# Controller_-_ESP32_Wroom_-_Rev_A.net
KiCad netlist of a schematic drawn in EAGLE
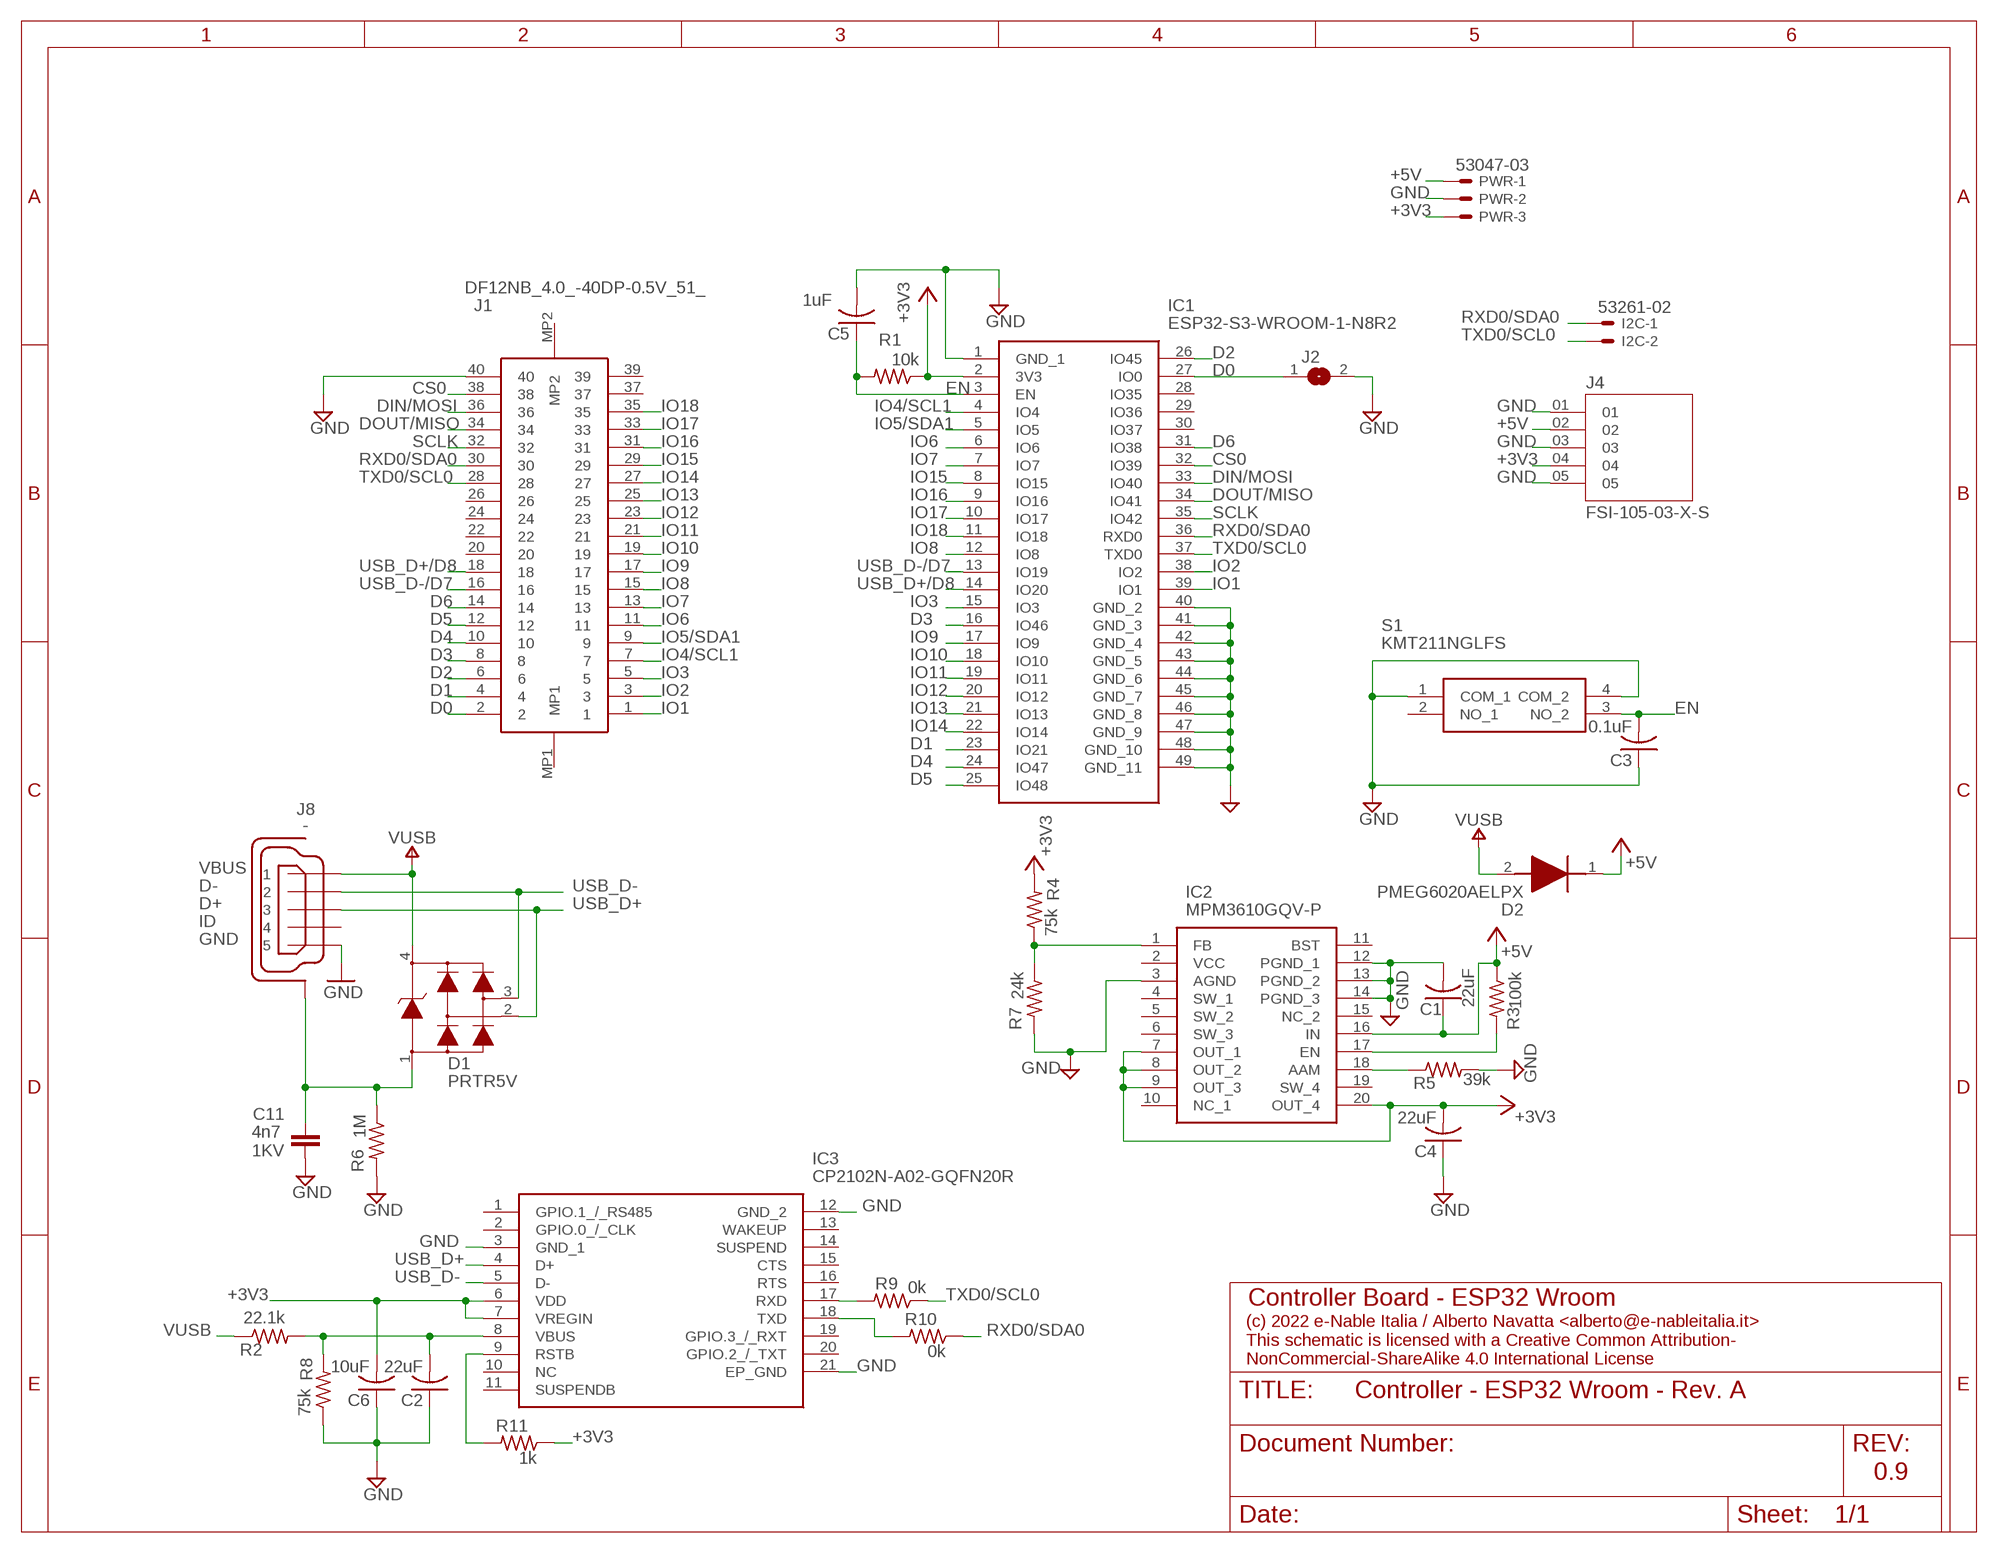
[diagram p0: schematic, sheet 1]

(export (version "E")
  (design (tool "Eeschema 10.0.6"))
  (components
    (comp (ref "C1")
      (value "22uF")
      (footprint "eagle-import:C0603")
      (libsource (lib "eagle-import") (part "C-USC0603"))
    )
    (comp (ref "C2")
      (value "22uF")
      (footprint "eagle-import:C0402")
      (libsource (lib "eagle-import") (part "C-USC0402"))
    )
    (comp (ref "C3")
      (value "0.1uF")
      (footprint "eagle-import:C0402")
      (libsource (lib "eagle-import") (part "C-USC0402"))
    )
    (comp (ref "C4")
      (value "22uF")
      (footprint "eagle-import:C0603")
      (libsource (lib "eagle-import") (part "C-USC0603"))
    )
    (comp (ref "C5")
      (value "1uF")
      (footprint "eagle-import:C0402")
      (libsource (lib "eagle-import") (part "C-USC0402"))
    )
    (comp (ref "C6")
      (value "10uF")
      (footprint "eagle-import:C0402")
      (libsource (lib "eagle-import") (part "C-USC0402"))
    )
    (comp (ref "C11")
      (value "4n7")
      (footprint "eagle-import:0805-R2013X50N")
      (fields (field (name "MANUFACTURER") "Kemet") (field (name "VOLTAGE") "1KV"))
      (libsource (lib "eagle-import") (part "C-08054.7NF"))
    )
    (comp (ref "D1")
      (value "PRTR5V")
      (footprint "eagle-import:SOT190P230X110-4N")
      (fields (field (name "MANUFACTURER") "NXP"))
      (libsource (lib "eagle-import") (part "PRTR5V0U2X,215"))
    )
    (comp (ref "D2")
      (value "PMEG6020AELPX")
      (footprint "eagle-import:SODFL4725X110N")
      (fields (field (name "MOUSER_PART_NUMBER") "771-PMEG6020AELPX"))
      (libsource (lib "eagle-import") (part "PMEG6020AELPX"))
    )
    (comp (ref "I2C")
      (value "53261-02")
      (footprint "eagle-import:53261-02")
      (fields (field (name "MF") "MOLEX"))
      (libsource (lib "eagle-import") (part "53?-02261"))
    )
    (comp (ref "IC1")
      (value "ESP32-S3-WROOM-1-N8R2")
      (footprint "eagle-import:ESP32S3WROOM1N8R2")
      (fields (field (name "MOUSER_PART_NUMBER") "356-ESP32-S3WRM1N8R2"))
      (libsource (lib "eagle-import") (part "ESP32-S3-WROOM-1-N8R2"))
    )
    (comp (ref "IC2")
      (value "MPM3610GQV-P")
      (footprint "eagle-import:MPM3610GQVP")
      (fields (field (name "MOUSER_PART_NUMBER") "946-MPM3610GQV-P"))
      (libsource (lib "eagle-import") (part "MPM3610GQV-P"))
    )
    (comp (ref "IC3")
      (value "CP2102N-A02-GQFN20R")
      (footprint "eagle-import:CP2102NA02GQFN20")
      (fields (field (name "MOUSER_PART_NUMBER") "634-CP2102NA02QFN20R"))
      (libsource (lib "eagle-import") (part "CP2102N-A02-GQFN20R"))
    )
    (comp (ref "J1")
      (value "DF12NB_4.0_-40DP-0.5V_51_")
      (footprint "eagle-import:DF12NB4040DP05V51")
      (fields
        (field (name "MANUFACTURER_PART_NUMBER") "DF12NB(4.0)-40DP-0.5V(51)")
        (field (name "MOUSER_PART_NUMBER") "798-DF12NB4040DP0551")
      )
      (libsource (lib "eagle-import") (part "DF12NB_4.0_-40DP-0.5V_51_"))
    )
    (comp (ref "J2") (value "SJ") (footprint "eagle-import:SJ") (libsource (lib "eagle-import") (part "SJ")))
    (comp (ref "J4")
      (value "FSI-105-03-X-S")
      (footprint "eagle-import:SAMTEC_FSI-105-03-X-S")
      (fields (field (name "MF") "Samtec") (field (name "MP") "FSI-105-03-G-S"))
      (libsource (lib "eagle-import") (part "FSI-105-03-X-S"))
    )
    (comp (ref "J8")
      (value "-")
      (footprint "eagle-import:ZX62-AB-5PA")
      (fields (field (name "MANUFACTURER") "Hirose"))
      (libsource (lib "eagle-import") (part "USB-MICRO"))
    )
    (comp (ref "PWR")
      (value "53047-03")
      (footprint "eagle-import:53047-03")
      (fields (field (name "MF") "MOLEX") (field (name "MPN") "530470310"))
      (libsource (lib "eagle-import") (part "53?-03047"))
    )
    (comp (ref "R1")
      (value "10k")
      (footprint "eagle-import:R0402")
      (libsource (lib "eagle-import") (part "R-US_R0402"))
    )
    (comp (ref "R2")
      (value "22.1k")
      (footprint "eagle-import:R0402")
      (libsource (lib "eagle-import") (part "R-US_R0402"))
    )
    (comp (ref "R3")
      (value "100k")
      (footprint "eagle-import:R0402")
      (libsource (lib "eagle-import") (part "R-US_R0402"))
    )
    (comp (ref "R4")
      (value "75k")
      (footprint "eagle-import:R0402")
      (libsource (lib "eagle-import") (part "R-US_R0402"))
    )
    (comp (ref "R5")
      (value "39k")
      (footprint "eagle-import:R0402")
      (libsource (lib "eagle-import") (part "R-US_R0402"))
    )
    (comp (ref "R6")
      (value "1M")
      (footprint "eagle-import:R0402")
      (libsource (lib "eagle-import") (part "R-US_R0402"))
    )
    (comp (ref "R7")
      (value "24k")
      (footprint "eagle-import:R0402")
      (libsource (lib "eagle-import") (part "R-US_R0402"))
    )
    (comp (ref "R8")
      (value "75k")
      (footprint "eagle-import:R0402")
      (libsource (lib "eagle-import") (part "R-US_R0402"))
    )
    (comp (ref "R9")
      (value "0k")
      (footprint "eagle-import:R0402")
      (libsource (lib "eagle-import") (part "R-US_R0402"))
    )
    (comp (ref "R10")
      (value "0k")
      (footprint "eagle-import:R0402")
      (libsource (lib "eagle-import") (part "R-US_R0402"))
    )
    (comp (ref "R11")
      (value "1k")
      (footprint "eagle-import:R0402")
      (libsource (lib "eagle-import") (part "R-US_R0402"))
    )
    (comp (ref "S1")
      (value "KMT211NGLFS")
      (footprint "eagle-import:KMT211NGLFS")
      (fields (field (name "MOUSER_PART_NUMBER") "611-KMT211NGLFS"))
      (libsource (lib "eagle-import") (part "KMT211NGLFS"))
    )
  )
  (nets
    (net (code "1") (name "+3V3") (class "Default")
      (node (ref "C4") (pin "2") (pinfunction "2_2") (pintype "passive"))
      (node (ref "C6") (pin "2") (pinfunction "2_2") (pintype "passive"))
      (node (ref "IC1") (pin "2") (pinfunction "3V3_2") (pintype "bidirectional"))
      (node (ref "IC2") (pin "20") (pinfunction "OUT_4_20") (pintype "bidirectional"))
      (node (ref "IC2") (pin "7") (pinfunction "OUT_1_7") (pintype "bidirectional"))
      (node (ref "IC2") (pin "8") (pinfunction "OUT_2_8") (pintype "bidirectional"))
      (node (ref "IC2") (pin "9") (pinfunction "OUT_3_9") (pintype "bidirectional"))
      (node (ref "IC3") (pin "6") (pinfunction "VDD_6") (pintype "bidirectional"))
      (node (ref "IC3") (pin "7") (pinfunction "VREGIN_7") (pintype "bidirectional"))
      (node (ref "J4") (pin "04") (pinfunction "04_04") (pintype "passive"))
      (node (ref "PWR") (pin "3") (pinfunction "S_3") (pintype "passive"))
      (node (ref "R1") (pin "1") (pinfunction "1_1") (pintype "passive"))
      (node (ref "R11") (pin "1") (pinfunction "1_1") (pintype "passive"))
      (node (ref "R4") (pin "2") (pinfunction "2_2") (pintype "passive"))
    )
    (net (code "2") (name "+5V") (class "Default")
      (node (ref "C1") (pin "1") (pinfunction "1_1") (pintype "passive"))
      (node (ref "D2") (pin "1") (pinfunction "K_1") (pintype "bidirectional"))
      (node (ref "IC2") (pin "16") (pinfunction "IN_16") (pintype "bidirectional"))
      (node (ref "J4") (pin "02") (pinfunction "02_02") (pintype "passive"))
      (node (ref "PWR") (pin "1") (pinfunction "S_1") (pintype "passive"))
      (node (ref "R3") (pin "1") (pinfunction "1_1") (pintype "passive"))
    )
    (net (code "3") (name "/CS0") (class "Default")
      (node (ref "IC1") (pin "32") (pinfunction "IO39_32") (pintype "bidirectional"))
      (node (ref "J1") (pin "38") (pinfunction "38_38") (pintype "bidirectional"))
    )
    (net (code "4") (name "/D0") (class "Default")
      (node (ref "IC1") (pin "27") (pinfunction "IO0_27") (pintype "bidirectional"))
      (node (ref "J1") (pin "2") (pinfunction "2_2") (pintype "bidirectional"))
      (node (ref "J2") (pin "1") (pinfunction "1_1") (pintype "passive"))
    )
    (net (code "5") (name "/D1") (class "Default")
      (node (ref "IC1") (pin "23") (pinfunction "IO21_23") (pintype "bidirectional"))
      (node (ref "J1") (pin "4") (pinfunction "4_4") (pintype "bidirectional"))
    )
    (net (code "6") (name "/D2") (class "Default")
      (node (ref "IC1") (pin "26") (pinfunction "IO45_26") (pintype "bidirectional"))
      (node (ref "J1") (pin "6") (pinfunction "6_6") (pintype "bidirectional"))
    )
    (net (code "7") (name "/D3") (class "Default")
      (node (ref "IC1") (pin "16") (pinfunction "IO46_16") (pintype "bidirectional"))
      (node (ref "J1") (pin "8") (pinfunction "8_8") (pintype "bidirectional"))
    )
    (net (code "8") (name "/D4") (class "Default")
      (node (ref "IC1") (pin "24") (pinfunction "IO47_24") (pintype "bidirectional"))
      (node (ref "J1") (pin "10") (pinfunction "10_10") (pintype "bidirectional"))
    )
    (net (code "9") (name "/D5") (class "Default")
      (node (ref "IC1") (pin "25") (pinfunction "IO48_25") (pintype "bidirectional"))
      (node (ref "J1") (pin "12") (pinfunction "12_12") (pintype "bidirectional"))
    )
    (net (code "10") (name "/D6") (class "Default")
      (node (ref "IC1") (pin "31") (pinfunction "IO38_31") (pintype "bidirectional"))
      (node (ref "J1") (pin "14") (pinfunction "14_14") (pintype "bidirectional"))
    )
    (net (code "11") (name "/DIN{slash}MOSI") (class "Default")
      (node (ref "IC1") (pin "33") (pinfunction "IO40_33") (pintype "bidirectional"))
      (node (ref "J1") (pin "36") (pinfunction "36_36") (pintype "bidirectional"))
    )
    (net (code "12") (name "/DOUT{slash}MISO") (class "Default")
      (node (ref "IC1") (pin "34") (pinfunction "IO41_34") (pintype "bidirectional"))
      (node (ref "J1") (pin "34") (pinfunction "34_34") (pintype "bidirectional"))
    )
    (net (code "13") (name "/EN") (class "Default")
      (node (ref "C3") (pin "2") (pinfunction "2_2") (pintype "passive"))
      (node (ref "C5") (pin "1") (pinfunction "1_1") (pintype "passive"))
      (node (ref "IC1") (pin "3") (pinfunction "EN_3") (pintype "bidirectional"))
      (node (ref "R1") (pin "2") (pinfunction "2_2") (pintype "passive"))
      (node (ref "S1") (pin "3") (pinfunction "NO_2_3") (pintype "bidirectional"))
    )
    (net (code "14") (name "/IO1") (class "Default")
      (node (ref "IC1") (pin "39") (pinfunction "IO1_39") (pintype "bidirectional"))
      (node (ref "J1") (pin "1") (pinfunction "1_1") (pintype "bidirectional"))
    )
    (net (code "15") (name "/IO2") (class "Default")
      (node (ref "IC1") (pin "38") (pinfunction "IO2_38") (pintype "bidirectional"))
      (node (ref "J1") (pin "3") (pinfunction "3_3") (pintype "bidirectional"))
    )
    (net (code "16") (name "/IO3") (class "Default")
      (node (ref "IC1") (pin "15") (pinfunction "IO3_15") (pintype "bidirectional"))
      (node (ref "J1") (pin "5") (pinfunction "5_5") (pintype "bidirectional"))
    )
    (net (code "17") (name "/IO4{slash}SCL1") (class "Default")
      (node (ref "IC1") (pin "4") (pinfunction "IO4_4") (pintype "bidirectional"))
      (node (ref "J1") (pin "7") (pinfunction "7_7") (pintype "bidirectional"))
    )
    (net (code "18") (name "/IO5{slash}SDA1") (class "Default")
      (node (ref "IC1") (pin "5") (pinfunction "IO5_5") (pintype "bidirectional"))
      (node (ref "J1") (pin "9") (pinfunction "9_9") (pintype "bidirectional"))
    )
    (net (code "19") (name "/IO6") (class "Default")
      (node (ref "IC1") (pin "6") (pinfunction "IO6_6") (pintype "bidirectional"))
      (node (ref "J1") (pin "11") (pinfunction "11_11") (pintype "bidirectional"))
    )
    (net (code "20") (name "/IO7") (class "Default")
      (node (ref "IC1") (pin "7") (pinfunction "IO7_7") (pintype "bidirectional"))
      (node (ref "J1") (pin "13") (pinfunction "13_13") (pintype "bidirectional"))
    )
    (net (code "21") (name "/IO8") (class "Default")
      (node (ref "IC1") (pin "12") (pinfunction "IO8_12") (pintype "bidirectional"))
      (node (ref "J1") (pin "15") (pinfunction "15_15") (pintype "bidirectional"))
    )
    (net (code "22") (name "/IO9") (class "Default")
      (node (ref "IC1") (pin "17") (pinfunction "IO9_17") (pintype "bidirectional"))
      (node (ref "J1") (pin "17") (pinfunction "17_17") (pintype "bidirectional"))
    )
    (net (code "23") (name "/IO10") (class "Default")
      (node (ref "IC1") (pin "18") (pinfunction "IO10_18") (pintype "bidirectional"))
      (node (ref "J1") (pin "19") (pinfunction "19_19") (pintype "bidirectional"))
    )
    (net (code "24") (name "/IO11") (class "Default")
      (node (ref "IC1") (pin "19") (pinfunction "IO11_19") (pintype "bidirectional"))
      (node (ref "J1") (pin "21") (pinfunction "21_21") (pintype "bidirectional"))
    )
    (net (code "25") (name "/IO12") (class "Default")
      (node (ref "IC1") (pin "20") (pinfunction "IO12_20") (pintype "bidirectional"))
      (node (ref "J1") (pin "23") (pinfunction "23_23") (pintype "bidirectional"))
    )
    (net (code "26") (name "/IO13") (class "Default")
      (node (ref "IC1") (pin "21") (pinfunction "IO13_21") (pintype "bidirectional"))
      (node (ref "J1") (pin "25") (pinfunction "25_25") (pintype "bidirectional"))
    )
    (net (code "27") (name "/IO14") (class "Default")
      (node (ref "IC1") (pin "22") (pinfunction "IO14_22") (pintype "bidirectional"))
      (node (ref "J1") (pin "27") (pinfunction "27_27") (pintype "bidirectional"))
    )
    (net (code "28") (name "/IO15") (class "Default")
      (node (ref "IC1") (pin "8") (pinfunction "IO15_8") (pintype "bidirectional"))
      (node (ref "J1") (pin "29") (pinfunction "29_29") (pintype "bidirectional"))
    )
    (net (code "29") (name "/IO16") (class "Default")
      (node (ref "IC1") (pin "9") (pinfunction "IO16_9") (pintype "bidirectional"))
      (node (ref "J1") (pin "31") (pinfunction "31_31") (pintype "bidirectional"))
    )
    (net (code "30") (name "/IO17") (class "Default")
      (node (ref "IC1") (pin "10") (pinfunction "IO17_10") (pintype "bidirectional"))
      (node (ref "J1") (pin "33") (pinfunction "33_33") (pintype "bidirectional"))
    )
    (net (code "31") (name "/IO18") (class "Default")
      (node (ref "IC1") (pin "11") (pinfunction "IO18_11") (pintype "bidirectional"))
      (node (ref "J1") (pin "35") (pinfunction "35_35") (pintype "bidirectional"))
    )
    (net (code "32") (name "/RXD0{slash}SDA0") (class "Default")
      (node (ref "I2C") (pin "1") (pinfunction "S_1") (pintype "passive"))
      (node (ref "IC1") (pin "36") (pinfunction "RXD0_36") (pintype "bidirectional"))
      (node (ref "J1") (pin "30") (pinfunction "30_30") (pintype "bidirectional"))
      (node (ref "R10") (pin "1") (pinfunction "1_1") (pintype "passive"))
    )
    (net (code "33") (name "/SCLK") (class "Default")
      (node (ref "IC1") (pin "35") (pinfunction "IO42_35") (pintype "bidirectional"))
      (node (ref "J1") (pin "32") (pinfunction "32_32") (pintype "bidirectional"))
    )
    (net (code "34") (name "/TXD0{slash}SCL0") (class "Default")
      (node (ref "I2C") (pin "2") (pinfunction "S_2") (pintype "passive"))
      (node (ref "IC1") (pin "37") (pinfunction "TXD0_37") (pintype "bidirectional"))
      (node (ref "J1") (pin "28") (pinfunction "28_28") (pintype "bidirectional"))
      (node (ref "R9") (pin "1") (pinfunction "1_1") (pintype "passive"))
    )
    (net (code "35") (name "/USB_D+") (class "Default")
      (node (ref "D1") (pin "2") (pinfunction "2_2") (pintype "passive"))
      (node (ref "IC3") (pin "4") (pinfunction "D+_4") (pintype "bidirectional"))
      (node (ref "J8") (pin "3") (pinfunction "3_3") (pintype "passive"))
    )
    (net (code "36") (name "/USB_D+{slash}D8") (class "Default")
      (node (ref "IC1") (pin "14") (pinfunction "IO20_14") (pintype "bidirectional"))
      (node (ref "J1") (pin "18") (pinfunction "18_18") (pintype "bidirectional"))
    )
    (net (code "37") (name "/USB_D-") (class "Default")
      (node (ref "D1") (pin "3") (pinfunction "3_3") (pintype "passive"))
      (node (ref "IC3") (pin "5") (pinfunction "D-_5") (pintype "bidirectional"))
      (node (ref "J8") (pin "2") (pinfunction "2_2") (pintype "passive"))
    )
    (net (code "38") (name "/USB_D-{slash}D7") (class "Default")
      (node (ref "IC1") (pin "13") (pinfunction "IO19_13") (pintype "bidirectional"))
      (node (ref "J1") (pin "16") (pinfunction "16_16") (pintype "bidirectional"))
    )
    (net (code "39") (name "GND") (class "Default")
      (node (ref "C1") (pin "2") (pinfunction "2_2") (pintype "passive"))
      (node (ref "C11") (pin "2") (pinfunction "2_2") (pintype "passive"))
      (node (ref "C2") (pin "1") (pinfunction "1_1") (pintype "passive"))
      (node (ref "C3") (pin "1") (pinfunction "1_1") (pintype "passive"))
      (node (ref "C4") (pin "1") (pinfunction "1_1") (pintype "passive"))
      (node (ref "C5") (pin "2") (pinfunction "2_2") (pintype "passive"))
      (node (ref "C6") (pin "1") (pinfunction "1_1") (pintype "passive"))
      (node (ref "IC1") (pin "1") (pinfunction "GND_1_1") (pintype "bidirectional"))
      (node (ref "IC1") (pin "40") (pinfunction "GND_2_40") (pintype "bidirectional"))
      (node (ref "IC1") (pin "41") (pinfunction "GND_3_41") (pintype "bidirectional"))
      (node (ref "IC1") (pin "42") (pinfunction "GND_4_42") (pintype "bidirectional"))
      (node (ref "IC1") (pin "43") (pinfunction "GND_5_43") (pintype "bidirectional"))
      (node (ref "IC1") (pin "44") (pinfunction "GND_6_44") (pintype "bidirectional"))
      (node (ref "IC1") (pin "45") (pinfunction "GND_7_45") (pintype "bidirectional"))
      (node (ref "IC1") (pin "46") (pinfunction "GND_8_46") (pintype "bidirectional"))
      (node (ref "IC1") (pin "47") (pinfunction "GND_9_47") (pintype "bidirectional"))
      (node (ref "IC1") (pin "48") (pinfunction "GND_10_48") (pintype "bidirectional"))
      (node (ref "IC1") (pin "49") (pinfunction "GND_11_49") (pintype "bidirectional"))
      (node (ref "IC2") (pin "12") (pinfunction "PGND_1_12") (pintype "bidirectional"))
      (node (ref "IC2") (pin "13") (pinfunction "PGND_2_13") (pintype "bidirectional"))
      (node (ref "IC2") (pin "14") (pinfunction "PGND_3_14") (pintype "bidirectional"))
      (node (ref "IC2") (pin "3") (pinfunction "AGND_3") (pintype "bidirectional"))
      (node (ref "IC3") (pin "12") (pinfunction "GND_2_12") (pintype "bidirectional"))
      (node (ref "IC3") (pin "21") (pinfunction "EP_GND_21") (pintype "bidirectional"))
      (node (ref "IC3") (pin "3") (pinfunction "GND_1_3") (pintype "bidirectional"))
      (node (ref "J1") (pin "40") (pinfunction "40_40") (pintype "bidirectional"))
      (node (ref "J2") (pin "2") (pinfunction "2_2") (pintype "passive"))
      (node (ref "J4") (pin "01") (pinfunction "01_01") (pintype "passive"))
      (node (ref "J4") (pin "03") (pinfunction "03_03") (pintype "passive"))
      (node (ref "J4") (pin "05") (pinfunction "05_05") (pintype "passive"))
      (node (ref "J8") (pin "5") (pinfunction "5_5") (pintype "passive"))
      (node (ref "PWR") (pin "2") (pinfunction "S_2") (pintype "passive"))
      (node (ref "R5") (pin "2") (pinfunction "2_2") (pintype "passive"))
      (node (ref "R6") (pin "2") (pinfunction "2_2") (pintype "passive"))
      (node (ref "R7") (pin "2") (pinfunction "2_2") (pintype "passive"))
      (node (ref "R8") (pin "1") (pinfunction "1_1") (pintype "passive"))
      (node (ref "S1") (pin "1") (pinfunction "COM_1_1") (pintype "bidirectional"))
      (node (ref "S1") (pin "4") (pinfunction "COM_2_4") (pintype "bidirectional"))
    )
    (net (code "40") (name "Net-(C11-Pad1)") (class "Default")
      (node (ref "C11") (pin "1") (pinfunction "1_1") (pintype "passive"))
      (node (ref "D1") (pin "1") (pinfunction "1_1") (pintype "passive"))
      (node (ref "J8") (pin "10") (pinfunction "SH_10") (pintype "passive"))
      (node (ref "J8") (pin "11") (pinfunction "SH_11") (pintype "passive"))
      (node (ref "J8") (pin "6") (pinfunction "SH_6") (pintype "passive"))
      (node (ref "J8") (pin "7") (pinfunction "SH_7") (pintype "passive"))
      (node (ref "J8") (pin "8") (pinfunction "SH_8") (pintype "passive"))
      (node (ref "J8") (pin "9") (pinfunction "SH_9") (pintype "passive"))
      (node (ref "R6") (pin "1") (pinfunction "1_1") (pintype "passive"))
    )
    (net (code "41") (name "Net-(IC2-AAM)") (class "Default")
      (node (ref "IC2") (pin "18") (pinfunction "AAM_18") (pintype "bidirectional"))
      (node (ref "R5") (pin "1") (pinfunction "1_1") (pintype "passive"))
    )
    (net (code "42") (name "Net-(IC2-EN)") (class "Default")
      (node (ref "IC2") (pin "17") (pinfunction "EN_17") (pintype "bidirectional"))
      (node (ref "R3") (pin "2") (pinfunction "2_2") (pintype "passive"))
    )
    (net (code "43") (name "Net-(IC2-FB)") (class "Default")
      (node (ref "IC2") (pin "1") (pinfunction "FB_1") (pintype "bidirectional"))
      (node (ref "R4") (pin "1") (pinfunction "1_1") (pintype "passive"))
      (node (ref "R7") (pin "1") (pinfunction "1_1") (pintype "passive"))
    )
    (net (code "44") (name "Net-(IC3-RSTB)") (class "Default")
      (node (ref "IC3") (pin "9") (pinfunction "RSTB_9") (pintype "bidirectional"))
      (node (ref "R11") (pin "2") (pinfunction "2_2") (pintype "passive"))
    )
    (net (code "45") (name "Net-(IC3-RXD)") (class "Default")
      (node (ref "IC3") (pin "17") (pinfunction "RXD_17") (pintype "bidirectional"))
      (node (ref "R9") (pin "2") (pinfunction "2_2") (pintype "passive"))
    )
    (net (code "46") (name "Net-(IC3-TXD)") (class "Default")
      (node (ref "IC3") (pin "18") (pinfunction "TXD_18") (pintype "bidirectional"))
      (node (ref "R10") (pin "2") (pinfunction "2_2") (pintype "passive"))
    )
    (net (code "47") (name "Net-(IC3-VBUS)") (class "Default")
      (node (ref "C2") (pin "2") (pinfunction "2_2") (pintype "passive"))
      (node (ref "IC3") (pin "8") (pinfunction "VBUS_8") (pintype "bidirectional"))
      (node (ref "R2") (pin "2") (pinfunction "2_2") (pintype "passive"))
      (node (ref "R8") (pin "2") (pinfunction "2_2") (pintype "passive"))
    )
    (net (code "48") (name "VUSB") (class "Default")
      (node (ref "D1") (pin "4") (pinfunction "4_4") (pintype "passive"))
      (node (ref "D2") (pin "2") (pinfunction "A_2") (pintype "bidirectional"))
      (node (ref "J8") (pin "1") (pinfunction "1_1") (pintype "passive"))
      (node (ref "R2") (pin "1") (pinfunction "1_1") (pintype "passive"))
    )
    (net (code "49") (name "unconnected-(IC1-IO35-Pad28)") (class "Default")
      (node (ref "IC1") (pin "28") (pinfunction "IO35_28") (pintype "bidirectional"))
    )
    (net (code "50") (name "unconnected-(IC1-IO36-Pad29)") (class "Default")
      (node (ref "IC1") (pin "29") (pinfunction "IO36_29") (pintype "bidirectional"))
    )
    (net (code "51") (name "unconnected-(IC1-IO37-Pad30)") (class "Default")
      (node (ref "IC1") (pin "30") (pinfunction "IO37_30") (pintype "bidirectional"))
    )
    (net (code "52") (name "unconnected-(IC2-BST-Pad11)") (class "Default")
      (node (ref "IC2") (pin "11") (pinfunction "BST_11") (pintype "bidirectional"))
    )
    (net (code "53") (name "unconnected-(IC2-NC_1-Pad10)") (class "Default")
      (node (ref "IC2") (pin "10") (pinfunction "NC_1_10") (pintype "bidirectional"))
    )
    (net (code "54") (name "unconnected-(IC2-NC_2-Pad15)") (class "Default")
      (node (ref "IC2") (pin "15") (pinfunction "NC_2_15") (pintype "bidirectional"))
    )
    (net (code "55") (name "unconnected-(IC2-SW_1-Pad4)") (class "Default")
      (node (ref "IC2") (pin "4") (pinfunction "SW_1_4") (pintype "bidirectional"))
    )
    (net (code "56") (name "unconnected-(IC2-SW_2-Pad5)") (class "Default")
      (node (ref "IC2") (pin "5") (pinfunction "SW_2_5") (pintype "bidirectional"))
    )
    (net (code "57") (name "unconnected-(IC2-SW_3-Pad6)") (class "Default")
      (node (ref "IC2") (pin "6") (pinfunction "SW_3_6") (pintype "bidirectional"))
    )
    (net (code "58") (name "unconnected-(IC2-SW_4-Pad19)") (class "Default")
      (node (ref "IC2") (pin "19") (pinfunction "SW_4_19") (pintype "bidirectional"))
    )
    (net (code "59") (name "unconnected-(IC2-VCC-Pad2)") (class "Default")
      (node (ref "IC2") (pin "2") (pinfunction "VCC_2") (pintype "bidirectional"))
    )
    (net (code "60") (name "unconnected-(IC3-CTS-Pad15)") (class "Default")
      (node (ref "IC3") (pin "15") (pinfunction "CTS_15") (pintype "bidirectional"))
    )
    (net (code "61") (name "unconnected-(IC3-GPIO.0_{slash}_CLK-Pad2)") (class "Default")
      (node (ref "IC3") (pin "2") (pinfunction "GPIO.0_/_CLK_2") (pintype "bidirectional"))
    )
    (net (code "62") (name "unconnected-(IC3-GPIO.1_{slash}_RS485-Pad1)") (class "Default")
      (node (ref "IC3") (pin "1") (pinfunction "GPIO.1_/_RS485_1") (pintype "bidirectional"))
    )
    (net (code "63") (name "unconnected-(IC3-GPIO.2_{slash}_TXT-Pad20)") (class "Default")
      (node (ref "IC3") (pin "20") (pinfunction "GPIO.2_/_TXT_20") (pintype "bidirectional"))
    )
    (net (code "64") (name "unconnected-(IC3-GPIO.3_{slash}_RXT-Pad19)") (class "Default")
      (node (ref "IC3") (pin "19") (pinfunction "GPIO.3_/_RXT_19") (pintype "bidirectional"))
    )
    (net (code "65") (name "unconnected-(IC3-NC-Pad10)") (class "Default")
      (node (ref "IC3") (pin "10") (pinfunction "NC_10") (pintype "no_connect"))
    )
    (net (code "66") (name "unconnected-(IC3-RTS-Pad16)") (class "Default")
      (node (ref "IC3") (pin "16") (pinfunction "RTS_16") (pintype "bidirectional"))
    )
    (net (code "67") (name "unconnected-(IC3-SUSPEND-Pad14)") (class "Default")
      (node (ref "IC3") (pin "14") (pinfunction "SUSPEND_14") (pintype "bidirectional"))
    )
    (net (code "68") (name "unconnected-(IC3-SUSPENDB-Pad11)") (class "Default")
      (node (ref "IC3") (pin "11") (pinfunction "SUSPENDB_11") (pintype "bidirectional"))
    )
    (net (code "69") (name "unconnected-(IC3-WAKEUP-Pad13)") (class "Default")
      (node (ref "IC3") (pin "13") (pinfunction "WAKEUP_13") (pintype "bidirectional"))
    )
    (net (code "70") (name "unconnected-(J1-Pad20)") (class "Default")
      (node (ref "J1") (pin "20") (pinfunction "20_20") (pintype "bidirectional"))
    )
    (net (code "71") (name "unconnected-(J1-Pad22)") (class "Default")
      (node (ref "J1") (pin "22") (pinfunction "22_22") (pintype "bidirectional"))
    )
    (net (code "72") (name "unconnected-(J1-Pad24)") (class "Default")
      (node (ref "J1") (pin "24") (pinfunction "24_24") (pintype "bidirectional"))
    )
    (net (code "73") (name "unconnected-(J1-Pad26)") (class "Default")
      (node (ref "J1") (pin "26") (pinfunction "26_26") (pintype "bidirectional"))
    )
    (net (code "74") (name "unconnected-(J1-Pad37)") (class "Default")
      (node (ref "J1") (pin "37") (pinfunction "37_37") (pintype "bidirectional"))
    )
    (net (code "75") (name "unconnected-(J1-Pad39)") (class "Default")
      (node (ref "J1") (pin "39") (pinfunction "39_39") (pintype "bidirectional"))
    )
    (net (code "76") (name "unconnected-(J1-PadMP1)") (class "Default")
      (node (ref "J1") (pin "MP1") (pinfunction "MP1_MP1") (pintype "bidirectional"))
    )
    (net (code "77") (name "unconnected-(J1-PadMP2)") (class "Default")
      (node (ref "J1") (pin "MP2") (pinfunction "MP2_MP2") (pintype "bidirectional"))
    )
    (net (code "78") (name "unconnected-(J8-Pad4)") (class "Default")
      (node (ref "J8") (pin "4") (pinfunction "4_4") (pintype "passive"))
    )
    (net (code "79") (name "unconnected-(S1-NO_1-Pad2)") (class "Default")
      (node (ref "S1") (pin "2") (pinfunction "NO_1_2") (pintype "bidirectional"))
    )
  )
)
